# Power_Circuit.net
KiCad netlist of a schematic drawn in Altium Designer
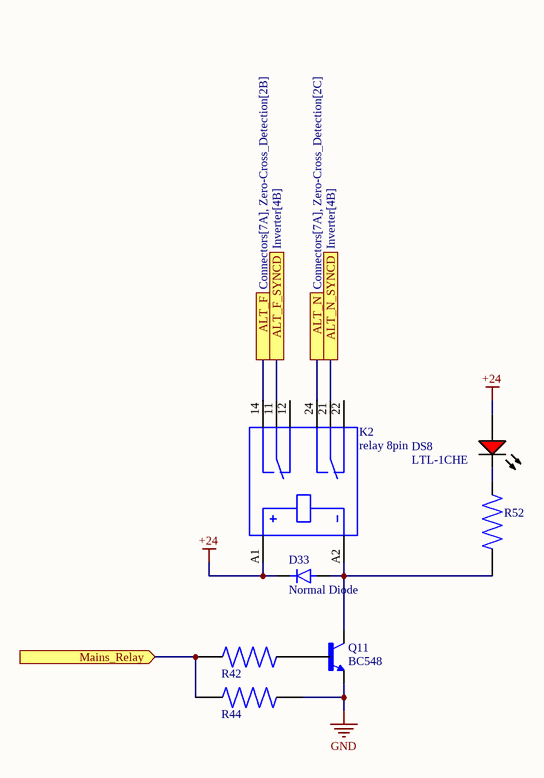
[diagram p0: Power Circuit.SchDoc]

(export (version "E")
  (design (tool "Eeschema 10.0.6"))
  (components
    (comp (ref "D33")
      (value "Normal Diode")
      (footprint "Common Trhough Hole")
      (fields (field (name "MF") "NTE Electronics, Inc.") (field (name "MP") "1N4007"))
      (libsource (lib "Diodes Through Hole") (part "Normal Diode"))
    )
    (comp (ref "DS8")
      (value "LTL-1CHE")
      (footprint "LED3mm")
      (description "Radial LED, 12.6 mcd, 20 mA, 2 V, -55 to 100 degC, 2-Pin THD, RoHS, Bulk")
      (fields (field (name "TOLERANCE") "20%"))
      (libsource (lib "MySCH_Library") (part "RED_LED 3mm"))
    )
    (comp (ref "K2")
      (value "relay 8pin")
      (footprint "Relay socket 8pin")
      (description "General Purpose Relay DPDT _2 Form C_ 24VDC Coil Through Hole")
      (fields (field (name "MF") "TE Connectivity") (field (name "MP") "1-1393243-0"))
      (libsource (lib "MySCH_Library") (part "relay 8pin"))
    )
    (comp (ref "Q11")
      (value "BC548")
      (footprint "bc548")
      (description "Bipolar (BJT) Transistor NPN 30V 100mA 300MHz 500mW Through Hole TO-92-3")
      (fields (field (name "MF") "ON Semiconductor"))
      (libsource (lib "MySCH_Library") (part "BC548"))
    )
    (comp (ref "R42")
      (value "Resistor_Through Hole")
      (footprint "Resistor_Through Hole")
      (description "1.02 Ohms Â±1% 0.25W, 1/4W Through Hole Resistor Axial Metal Film")
      (fields (field (name "MP") "MFR-25FTE52-1R") (field (name "MF") "Yageo"))
      (libsource (lib "MySCH_Library") (part "Resistor_Through Hole"))
    )
    (comp (ref "R44")
      (value "Resistor_Through Hole")
      (footprint "Resistor_Through Hole")
      (description "1.02 Ohms Â±1% 0.25W, 1/4W Through Hole Resistor Axial Metal Film")
      (fields (field (name "MP") "MFR-25FTE52-1R") (field (name "MF") "Yageo"))
      (libsource (lib "MySCH_Library") (part "Resistor_Through Hole"))
    )
    (comp (ref "R52")
      (value "Resistor_Through Hole")
      (footprint "Resistor_Through Hole")
      (description "1.02 Ohms Â±1% 0.25W, 1/4W Through Hole Resistor Axial Metal Film")
      (fields (field (name "MP") "MFR-25FTE52-1R") (field (name "MF") "Yageo"))
      (libsource (lib "MySCH_Library") (part "Resistor_Through Hole"))
    )
  )
  (nets
    (net (code "1") (name "+24") (class "Default")
      (node (ref "D33") (pin "1") (pinfunction "K_1") (pintype "passive"))
      (node (ref "DS8") (pin "1") (pinfunction "A_1") (pintype "passive"))
      (node (ref "K2") (pin "A1") (pinfunction "1_A1") (pintype "passive"))
    )
    (net (code "2") (name "/ALT_F") (class "Default")
      (node (ref "K2") (pin "14") (pinfunction "5_14") (pintype "passive"))
    )
    (net (code "3") (name "/ALT_F_SYNCD") (class "Default")
      (node (ref "K2") (pin "11") (pinfunction "6_11") (pintype "passive"))
    )
    (net (code "4") (name "/ALT_N") (class "Default")
      (node (ref "K2") (pin "24") (pinfunction "4_24") (pintype "passive"))
    )
    (net (code "5") (name "/ALT_N_SYNCD") (class "Default")
      (node (ref "K2") (pin "21") (pinfunction "3_21") (pintype "passive"))
    )
    (net (code "6") (name "/Mains_Relay") (class "Default")
      (node (ref "R42") (pin "2") (pinfunction "2_2") (pintype "passive"))
      (node (ref "R44") (pin "2") (pinfunction "2_2") (pintype "passive"))
    )
    (net (code "7") (name "GND") (class "Default")
      (node (ref "Q11") (pin "3") (pinfunction "E_3") (pintype "passive"))
      (node (ref "R44") (pin "1") (pinfunction "1_1") (pintype "passive"))
    )
    (net (code "8") (name "Net-(D33-A)") (class "Default")
      (node (ref "D33") (pin "2") (pinfunction "A_2") (pintype "passive"))
      (node (ref "K2") (pin "A2") (pinfunction "8_A2") (pintype "passive"))
      (node (ref "Q11") (pin "1") (pinfunction "C_1") (pintype "passive"))
      (node (ref "R52") (pin "2") (pinfunction "2_2") (pintype "passive"))
    )
    (net (code "9") (name "Net-(DS8-K)") (class "Default")
      (node (ref "DS8") (pin "2") (pinfunction "K_2") (pintype "passive"))
      (node (ref "R52") (pin "1") (pinfunction "1_1") (pintype "passive"))
    )
    (net (code "10") (name "Net-(Q11-B)") (class "Default")
      (node (ref "Q11") (pin "2") (pinfunction "B_2") (pintype "passive"))
      (node (ref "R42") (pin "1") (pinfunction "1_1") (pintype "passive"))
    )
    (net (code "11") (name "unconnected-(K2-2-Pad22)") (class "Default")
      (node (ref "K2") (pin "22") (pinfunction "2_22") (pintype "passive"))
    )
    (net (code "12") (name "unconnected-(K2-7-Pad12)") (class "Default")
      (node (ref "K2") (pin "12") (pinfunction "7_12") (pintype "passive"))
    )
  )
)
